# Comparator_Breakout_MAX9031.net
KiCad netlist of a schematic drawn in EAGLE
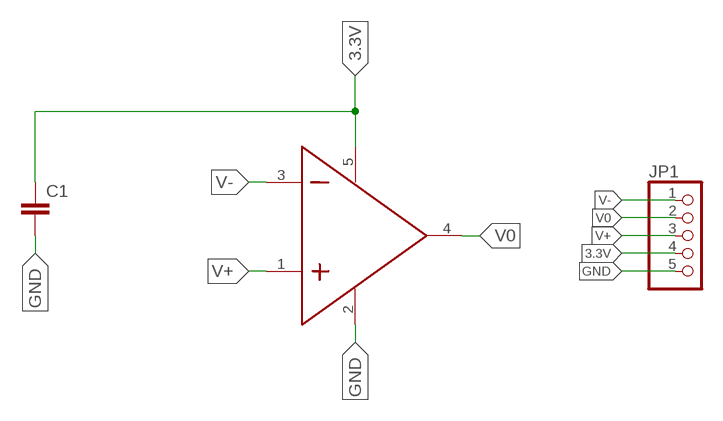
[diagram p0: schematic, sheet 1]

(export (version "E")
  (design (tool "Eeschema 10.0.6"))
  (components
    (comp (ref "C1")
      (value "C-EUC0805")
      (footprint "eagle-import:C0805")
      (libsource (lib "eagle-import") (part "C-EUC0805"))
    )
    (comp (ref "JP1")
      (value "PINHD-1X5")
      (footprint "eagle-import:1X05")
      (libsource (lib "eagle-import") (part "PINHD-1X5"))
    )
    (comp (ref "U$1")
      (value "MAX9031")
      (footprint "eagle-import:SOT23-5")
      (libsource (lib "eagle-import") (part "MAX9031"))
    )
  )
  (nets
    (net (code "1") (name "3.3V") (class "Default")
      (node (ref "C1") (pin "1") (pinfunction "1_1") (pintype "passive"))
      (node (ref "JP1") (pin "4") (pinfunction "4_4") (pintype "passive"))
      (node (ref "U$1") (pin "5") (pinfunction "VDD_5") (pintype "bidirectional"))
    )
    (net (code "2") (name "GND") (class "Default")
      (node (ref "C1") (pin "2") (pinfunction "2_2") (pintype "passive"))
      (node (ref "JP1") (pin "5") (pinfunction "5_5") (pintype "passive"))
      (node (ref "U$1") (pin "2") (pinfunction "VSS_2") (pintype "bidirectional"))
    )
    (net (code "3") (name "V+") (class "Default")
      (node (ref "JP1") (pin "3") (pinfunction "3_3") (pintype "passive"))
      (node (ref "U$1") (pin "1") (pinfunction "IN+_1") (pintype "bidirectional"))
    )
    (net (code "4") (name "V-") (class "Default")
      (node (ref "JP1") (pin "1") (pinfunction "1_1") (pintype "passive"))
      (node (ref "U$1") (pin "3") (pinfunction "IN-_3") (pintype "bidirectional"))
    )
    (net (code "5") (name "V0") (class "Default")
      (node (ref "JP1") (pin "2") (pinfunction "2_2") (pintype "passive"))
      (node (ref "U$1") (pin "4") (pinfunction "OUT_4") (pintype "bidirectional"))
    )
  )
)
